# Block.net
KiCad netlist of a schematic drawn in Altium Designer
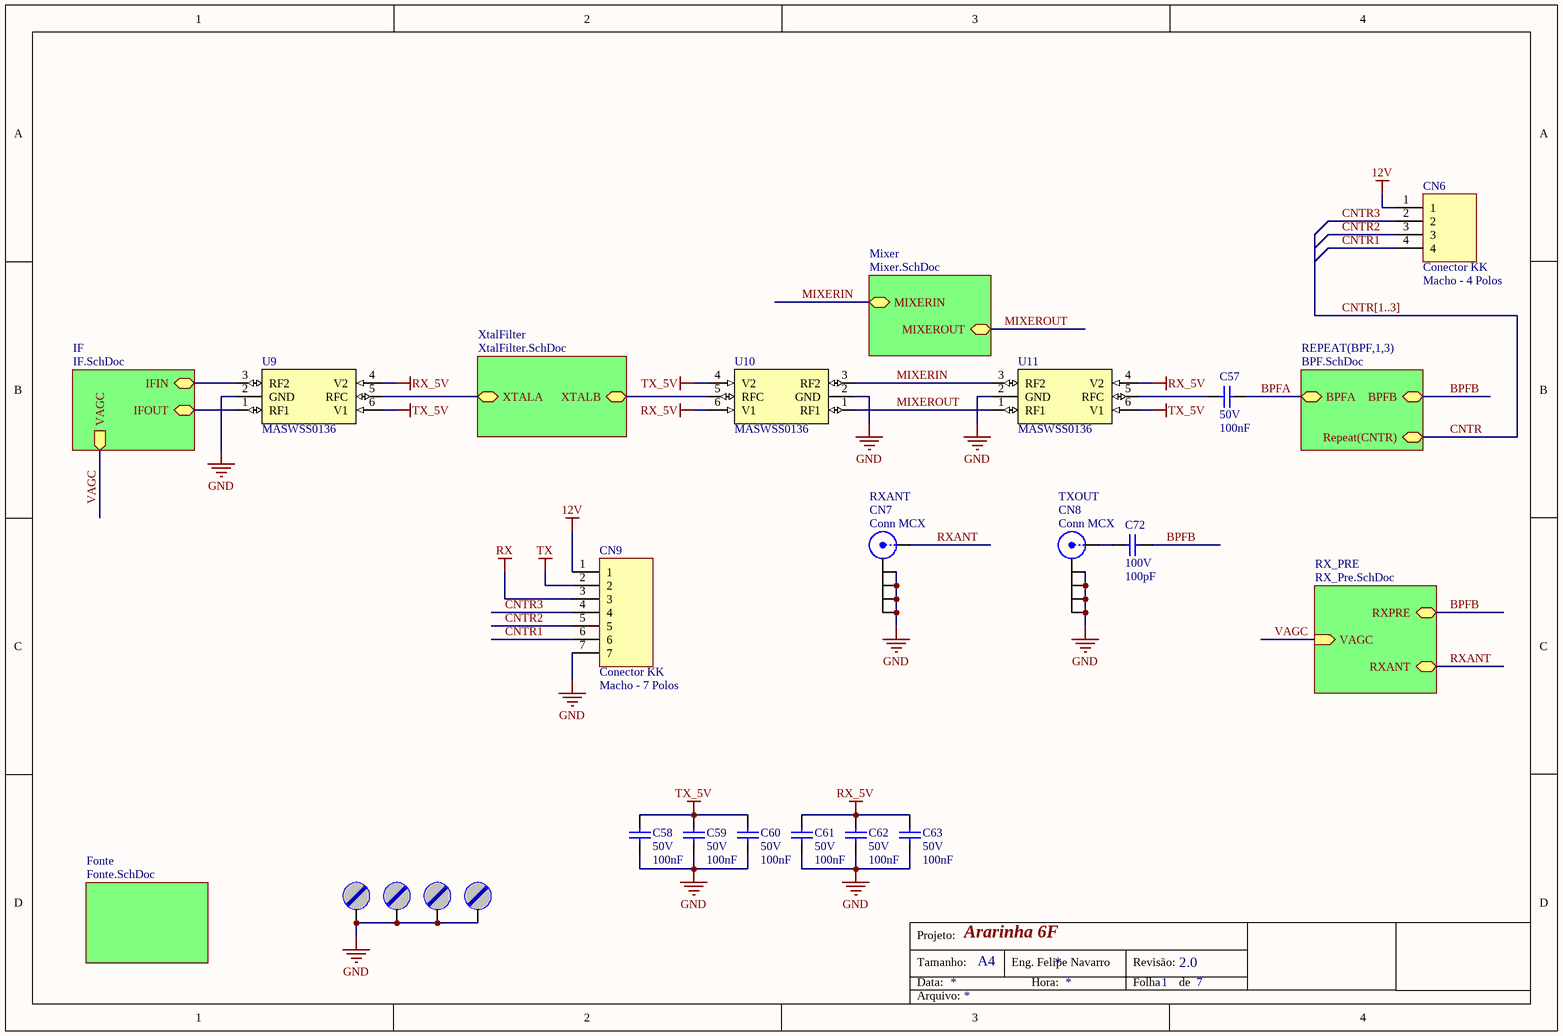
[diagram p0: Block.SchDoc]

(export (version "E")
  (design (tool "Eeschema 10.0.6"))
  (components
    (comp (ref "C57")
      (value "100nF")
      (footprint "CC0603")
      (description "Capacitor (Semiconductor SIM Model)")
      (fields (field (name "TENSÃO") "50V") (field (name "Comment") "Capacitor Cerâmico"))
      (libsource (lib "NavarroCAP") (part "Cap 100nF 50V 0603 X7R"))
    )
    (comp (ref "C58")
      (value "100nF")
      (footprint "CC0603")
      (description "Capacitor (Semiconductor SIM Model)")
      (fields (field (name "TENSÃO") "50V") (field (name "Comment") "Capacitor Cerâmico"))
      (libsource (lib "NavarroCAP") (part "Cap 100nF 50V 0603 X7R"))
    )
    (comp (ref "C59")
      (value "100nF")
      (footprint "CC0603")
      (description "Capacitor (Semiconductor SIM Model)")
      (fields (field (name "TENSÃO") "50V") (field (name "Comment") "Capacitor Cerâmico"))
      (libsource (lib "NavarroCAP") (part "Cap 100nF 50V 0603 X7R"))
    )
    (comp (ref "C60")
      (value "100nF")
      (footprint "CC0603")
      (description "Capacitor (Semiconductor SIM Model)")
      (fields (field (name "TENSÃO") "50V") (field (name "Comment") "Capacitor Cerâmico"))
      (libsource (lib "NavarroCAP") (part "Cap 100nF 50V 0603 X7R"))
    )
    (comp (ref "C61")
      (value "100nF")
      (footprint "CC0603")
      (description "Capacitor (Semiconductor SIM Model)")
      (fields (field (name "TENSÃO") "50V") (field (name "Comment") "Capacitor Cerâmico"))
      (libsource (lib "NavarroCAP") (part "Cap 100nF 50V 0603 X7R"))
    )
    (comp (ref "C62")
      (value "100nF")
      (footprint "CC0603")
      (description "Capacitor (Semiconductor SIM Model)")
      (fields (field (name "TENSÃO") "50V") (field (name "Comment") "Capacitor Cerâmico"))
      (libsource (lib "NavarroCAP") (part "Cap 100nF 50V 0603 X7R"))
    )
    (comp (ref "C63")
      (value "100nF")
      (footprint "CC0603")
      (description "Capacitor (Semiconductor SIM Model)")
      (fields (field (name "TENSÃO") "50V") (field (name "Comment") "Capacitor Cerâmico"))
      (libsource (lib "NavarroCAP") (part "Cap 100nF 50V 0603 X7R"))
    )
    (comp (ref "C72")
      (value "100pF")
      (footprint "CC0603")
      (description "Capacitor (Semiconductor SIM Model)")
      (fields (field (name "TENSÃO") "100V") (field (name "Comment") "Capacitor Cerâmico"))
      (libsource (lib "NavarroCAP") (part "Cap 100pF 100V 0603 NP0"))
    )
    (comp (ref "CN6")
      (value "Conector KK")
      (footprint "CONN HDR4-POL P.100")
      (fields (field (name "ALTIUM_VALUE") "Macho - 4 Polos"))
      (libsource (lib "NavarroCON") (part "KK 4P Macho-V P2.54mm"))
    )
    (comp (ref "CN7")
      (value "Conn MCX")
      (footprint "CONN MCX MOLEX")
      (description "Conector MCX")
      (libsource (lib "NavarroCON") (part "Conn MCX"))
    )
    (comp (ref "CN8")
      (value "Conn MCX")
      (footprint "CONN MCX MOLEX")
      (description "Conector MCX")
      (libsource (lib "NavarroCON") (part "Conn MCX"))
    )
    (comp (ref "CN9")
      (value "Conector KK")
      (footprint "CONN HDR7-POL P.100")
      (fields (field (name "ALTIUM_VALUE") "Macho - 7 Polos"))
      (libsource (lib "NavarroCON") (part "KK 7P Macho-V P2.54mm"))
    )
    (comp (ref "HOLE1")
      (value "Furo de Fixação")
      (footprint "Furo_M3")
      (description "Furo para parafuso")
      (libsource (lib "Navarro") (part "Parafuso"))
    )
    (comp (ref "HOLE2")
      (value "Furo de Fixação")
      (footprint "Furo_M3")
      (description "Furo para parafuso")
      (libsource (lib "Navarro") (part "Parafuso"))
    )
    (comp (ref "HOLE3")
      (value "Furo de Fixação")
      (footprint "Furo_M3")
      (description "Furo para parafuso")
      (libsource (lib "Navarro") (part "Parafuso"))
    )
    (comp (ref "HOLE4")
      (value "Furo de Fixação")
      (footprint "Furo_M3")
      (description "Furo para parafuso")
      (libsource (lib "Navarro") (part "Parafuso"))
    )
    (comp (ref "U9")
      (value "MASWSS0136")
      (footprint "SC70-6N")
      (description "GaAs SPDT Switch DC - 3.0 GHz")
      (libsource (lib "Navarro") (part "MASWSS0136"))
    )
    (comp (ref "U10")
      (value "MASWSS0136")
      (footprint "SC70-6N")
      (description "GaAs SPDT Switch DC - 3.0 GHz")
      (libsource (lib "") (part "MASWSS0136_1"))
    )
    (comp (ref "U11")
      (value "MASWSS0136")
      (footprint "SC70-6N")
      (description "GaAs SPDT Switch DC - 3.0 GHz")
      (libsource (lib "Navarro") (part "MASWSS0136"))
    )
  )
  (nets
    (net (code "1") (name "/BPFA") (class "Default")
      (node (ref "C57") (pin "2") (pinfunction "2_2") (pintype "passive"))
    )
    (net (code "2") (name "/BPFB") (class "Default")
      (node (ref "C72") (pin "2") (pinfunction "2_2") (pintype "passive"))
    )
    (net (code "4") (name "/CNTR1") (class "Default")
      (node (ref "CN6") (pin "4") (pinfunction "4_4") (pintype "passive"))
      (node (ref "CN9") (pin "6") (pinfunction "6_6") (pintype "passive"))
    )
    (net (code "5") (name "/CNTR2") (class "Default")
      (node (ref "CN6") (pin "3") (pinfunction "3_3") (pintype "passive"))
      (node (ref "CN9") (pin "5") (pinfunction "5_5") (pintype "passive"))
    )
    (net (code "6") (name "/CNTR3") (class "Default")
      (node (ref "CN6") (pin "2") (pinfunction "2_2") (pintype "passive"))
      (node (ref "CN9") (pin "4") (pinfunction "4_4") (pintype "passive"))
    )
    (net (code "8") (name "/IFIN") (class "Default")
      (node (ref "U9") (pin "3") (pinfunction "RF2_3") (pintype "bidirectional"))
    )
    (net (code "9") (name "/IFOUT") (class "Default")
      (node (ref "U9") (pin "1") (pinfunction "RF1_1") (pintype "bidirectional"))
    )
    (net (code "10") (name "/MIXERIN") (class "Default")
      (node (ref "U10") (pin "3") (pinfunction "RF2_3") (pintype "bidirectional"))
      (node (ref "U11") (pin "3") (pinfunction "RF2_3") (pintype "bidirectional"))
    )
    (net (code "11") (name "/MIXEROUT") (class "Default")
      (node (ref "U10") (pin "1") (pinfunction "RF1_1") (pintype "bidirectional"))
      (node (ref "U11") (pin "1") (pinfunction "RF1_1") (pintype "bidirectional"))
    )
    (net (code "12") (name "/RXANT") (class "Default")
      (node (ref "CN7") (pin "1") (pinfunction "X_1") (pintype "passive"))
    )
    (net (code "14") (name "/XTALA") (class "Default")
      (node (ref "U9") (pin "5") (pinfunction "RFC_5") (pintype "bidirectional"))
    )
    (net (code "15") (name "/XTALB") (class "Default")
      (node (ref "U10") (pin "5") (pinfunction "RFC_5") (pintype "bidirectional"))
    )
    (net (code "16") (name "12V") (class "Default")
      (node (ref "CN6") (pin "1") (pinfunction "1_1") (pintype "passive"))
      (node (ref "CN9") (pin "1") (pinfunction "1_1") (pintype "passive"))
    )
    (net (code "17") (name "GND") (class "Default")
      (node (ref "C58") (pin "1") (pinfunction "1_1") (pintype "passive"))
      (node (ref "C59") (pin "1") (pinfunction "1_1") (pintype "passive"))
      (node (ref "C60") (pin "1") (pinfunction "1_1") (pintype "passive"))
      (node (ref "C61") (pin "1") (pinfunction "1_1") (pintype "passive"))
      (node (ref "C62") (pin "1") (pinfunction "1_1") (pintype "passive"))
      (node (ref "C63") (pin "1") (pinfunction "1_1") (pintype "passive"))
      (node (ref "CN7") (pin "2") (pinfunction "Y_2") (pintype "passive"))
      (node (ref "CN7") (pin "3") (pinfunction "Y_3") (pintype "passive"))
      (node (ref "CN7") (pin "4") (pinfunction "Y_4") (pintype "passive"))
      (node (ref "CN7") (pin "5") (pinfunction "Y_5") (pintype "passive"))
      (node (ref "CN8") (pin "2") (pinfunction "Y_2") (pintype "passive"))
      (node (ref "CN8") (pin "3") (pinfunction "Y_3") (pintype "passive"))
      (node (ref "CN8") (pin "4") (pinfunction "Y_4") (pintype "passive"))
      (node (ref "CN8") (pin "5") (pinfunction "Y_5") (pintype "passive"))
      (node (ref "CN9") (pin "7") (pinfunction "7_7") (pintype "passive"))
      (node (ref "HOLE1") (pin "X") (pinfunction "X_X") (pintype "passive"))
      (node (ref "HOLE2") (pin "X") (pinfunction "X_X") (pintype "passive"))
      (node (ref "HOLE3") (pin "X") (pinfunction "X_X") (pintype "passive"))
      (node (ref "HOLE4") (pin "X") (pinfunction "X_X") (pintype "passive"))
      (node (ref "U10") (pin "2") (pinfunction "GND_2") (pintype "power_in"))
      (node (ref "U11") (pin "2") (pinfunction "GND_2") (pintype "power_in"))
      (node (ref "U9") (pin "2") (pinfunction "GND_2") (pintype "power_in"))
    )
    (net (code "18") (name "Net-(CN8-X)") (class "Default")
      (node (ref "C72") (pin "1") (pinfunction "1_1") (pintype "passive"))
      (node (ref "CN8") (pin "1") (pinfunction "X_1") (pintype "passive"))
    )
    (net (code "19") (name "Net-(U11-RFC)") (class "Default")
      (node (ref "C57") (pin "1") (pinfunction "1_1") (pintype "passive"))
      (node (ref "U11") (pin "5") (pinfunction "RFC_5") (pintype "bidirectional"))
    )
    (net (code "20") (name "RX") (class "Default")
      (node (ref "CN9") (pin "3") (pinfunction "3_3") (pintype "passive"))
    )
    (net (code "21") (name "RX_5V") (class "Default")
      (node (ref "C61") (pin "2") (pinfunction "2_2") (pintype "passive"))
      (node (ref "C62") (pin "2") (pinfunction "2_2") (pintype "passive"))
      (node (ref "C63") (pin "2") (pinfunction "2_2") (pintype "passive"))
      (node (ref "U10") (pin "6") (pinfunction "V1_6") (pintype "input"))
      (node (ref "U11") (pin "4") (pinfunction "V2_4") (pintype "input"))
      (node (ref "U9") (pin "4") (pinfunction "V2_4") (pintype "input"))
    )
    (net (code "22") (name "TX") (class "Default")
      (node (ref "CN9") (pin "2") (pinfunction "2_2") (pintype "passive"))
    )
    (net (code "23") (name "TX_5V") (class "Default")
      (node (ref "C58") (pin "2") (pinfunction "2_2") (pintype "passive"))
      (node (ref "C59") (pin "2") (pinfunction "2_2") (pintype "passive"))
      (node (ref "C60") (pin "2") (pinfunction "2_2") (pintype "passive"))
      (node (ref "U10") (pin "4") (pinfunction "V2_4") (pintype "input"))
      (node (ref "U11") (pin "6") (pinfunction "V1_6") (pintype "input"))
      (node (ref "U9") (pin "6") (pinfunction "V1_6") (pintype "input"))
    )
  )
)
